# dual_vca_jumper.net
KiCad netlist of a schematic drawn in EAGLE
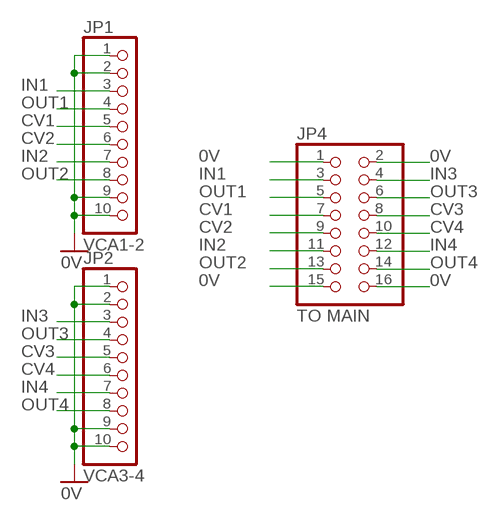
[diagram p0: schematic, sheet 1]

(export (version "E")
  (design (tool "Eeschema 10.0.6"))
  (components
    (comp (ref "JP1")
      (value "VCA1-2")
      (footprint "eagle-import:1X10")
      (libsource (lib "eagle-import") (part "PINHD-1X10"))
    )
    (comp (ref "JP2")
      (value "VCA3-4")
      (footprint "eagle-import:1X10")
      (libsource (lib "eagle-import") (part "PINHD-1X10"))
    )
    (comp (ref "JP4")
      (value "TO MAIN")
      (footprint "eagle-import:2X08")
      (libsource (lib "eagle-import") (part "PINHD-2X8"))
    )
  )
  (nets
    (net (code "1") (name "/CV1") (class "Default")
      (node (ref "JP1") (pin "5") (pinfunction "5_5") (pintype "passive"))
      (node (ref "JP4") (pin "7") (pinfunction "7_7") (pintype "passive"))
    )
    (net (code "2") (name "/CV2") (class "Default")
      (node (ref "JP1") (pin "6") (pinfunction "6_6") (pintype "passive"))
      (node (ref "JP4") (pin "9") (pinfunction "9_9") (pintype "passive"))
    )
    (net (code "3") (name "/CV3") (class "Default")
      (node (ref "JP2") (pin "5") (pinfunction "5_5") (pintype "passive"))
      (node (ref "JP4") (pin "8") (pinfunction "8_8") (pintype "passive"))
    )
    (net (code "4") (name "/CV4") (class "Default")
      (node (ref "JP2") (pin "6") (pinfunction "6_6") (pintype "passive"))
      (node (ref "JP4") (pin "10") (pinfunction "10_10") (pintype "passive"))
    )
    (net (code "5") (name "/IN1") (class "Default")
      (node (ref "JP1") (pin "3") (pinfunction "3_3") (pintype "passive"))
      (node (ref "JP4") (pin "3") (pinfunction "3_3") (pintype "passive"))
    )
    (net (code "6") (name "/IN2") (class "Default")
      (node (ref "JP1") (pin "7") (pinfunction "7_7") (pintype "passive"))
      (node (ref "JP4") (pin "11") (pinfunction "11_11") (pintype "passive"))
    )
    (net (code "7") (name "/IN3") (class "Default")
      (node (ref "JP2") (pin "3") (pinfunction "3_3") (pintype "passive"))
      (node (ref "JP4") (pin "4") (pinfunction "4_4") (pintype "passive"))
    )
    (net (code "8") (name "/IN4") (class "Default")
      (node (ref "JP2") (pin "7") (pinfunction "7_7") (pintype "passive"))
      (node (ref "JP4") (pin "12") (pinfunction "12_12") (pintype "passive"))
    )
    (net (code "9") (name "/OUT1") (class "Default")
      (node (ref "JP1") (pin "4") (pinfunction "4_4") (pintype "passive"))
      (node (ref "JP4") (pin "5") (pinfunction "5_5") (pintype "passive"))
    )
    (net (code "10") (name "/OUT2") (class "Default")
      (node (ref "JP1") (pin "8") (pinfunction "8_8") (pintype "passive"))
      (node (ref "JP4") (pin "13") (pinfunction "13_13") (pintype "passive"))
    )
    (net (code "11") (name "/OUT3") (class "Default")
      (node (ref "JP2") (pin "4") (pinfunction "4_4") (pintype "passive"))
      (node (ref "JP4") (pin "6") (pinfunction "6_6") (pintype "passive"))
    )
    (net (code "12") (name "/OUT4") (class "Default")
      (node (ref "JP2") (pin "8") (pinfunction "8_8") (pintype "passive"))
      (node (ref "JP4") (pin "14") (pinfunction "14_14") (pintype "passive"))
    )
    (net (code "13") (name "0V") (class "Default")
      (node (ref "JP1") (pin "1") (pinfunction "1_1") (pintype "passive"))
      (node (ref "JP1") (pin "10") (pinfunction "10_10") (pintype "passive"))
      (node (ref "JP1") (pin "2") (pinfunction "2_2") (pintype "passive"))
      (node (ref "JP1") (pin "9") (pinfunction "9_9") (pintype "passive"))
      (node (ref "JP2") (pin "1") (pinfunction "1_1") (pintype "passive"))
      (node (ref "JP2") (pin "10") (pinfunction "10_10") (pintype "passive"))
      (node (ref "JP2") (pin "2") (pinfunction "2_2") (pintype "passive"))
      (node (ref "JP2") (pin "9") (pinfunction "9_9") (pintype "passive"))
      (node (ref "JP4") (pin "1") (pinfunction "1_1") (pintype "passive"))
      (node (ref "JP4") (pin "15") (pinfunction "15_15") (pintype "passive"))
      (node (ref "JP4") (pin "16") (pinfunction "16_16") (pintype "passive"))
      (node (ref "JP4") (pin "2") (pinfunction "2_2") (pintype "passive"))
    )
  )
)
